# sBoardUS.net
KiCad netlist of a schematic drawn in EAGLE
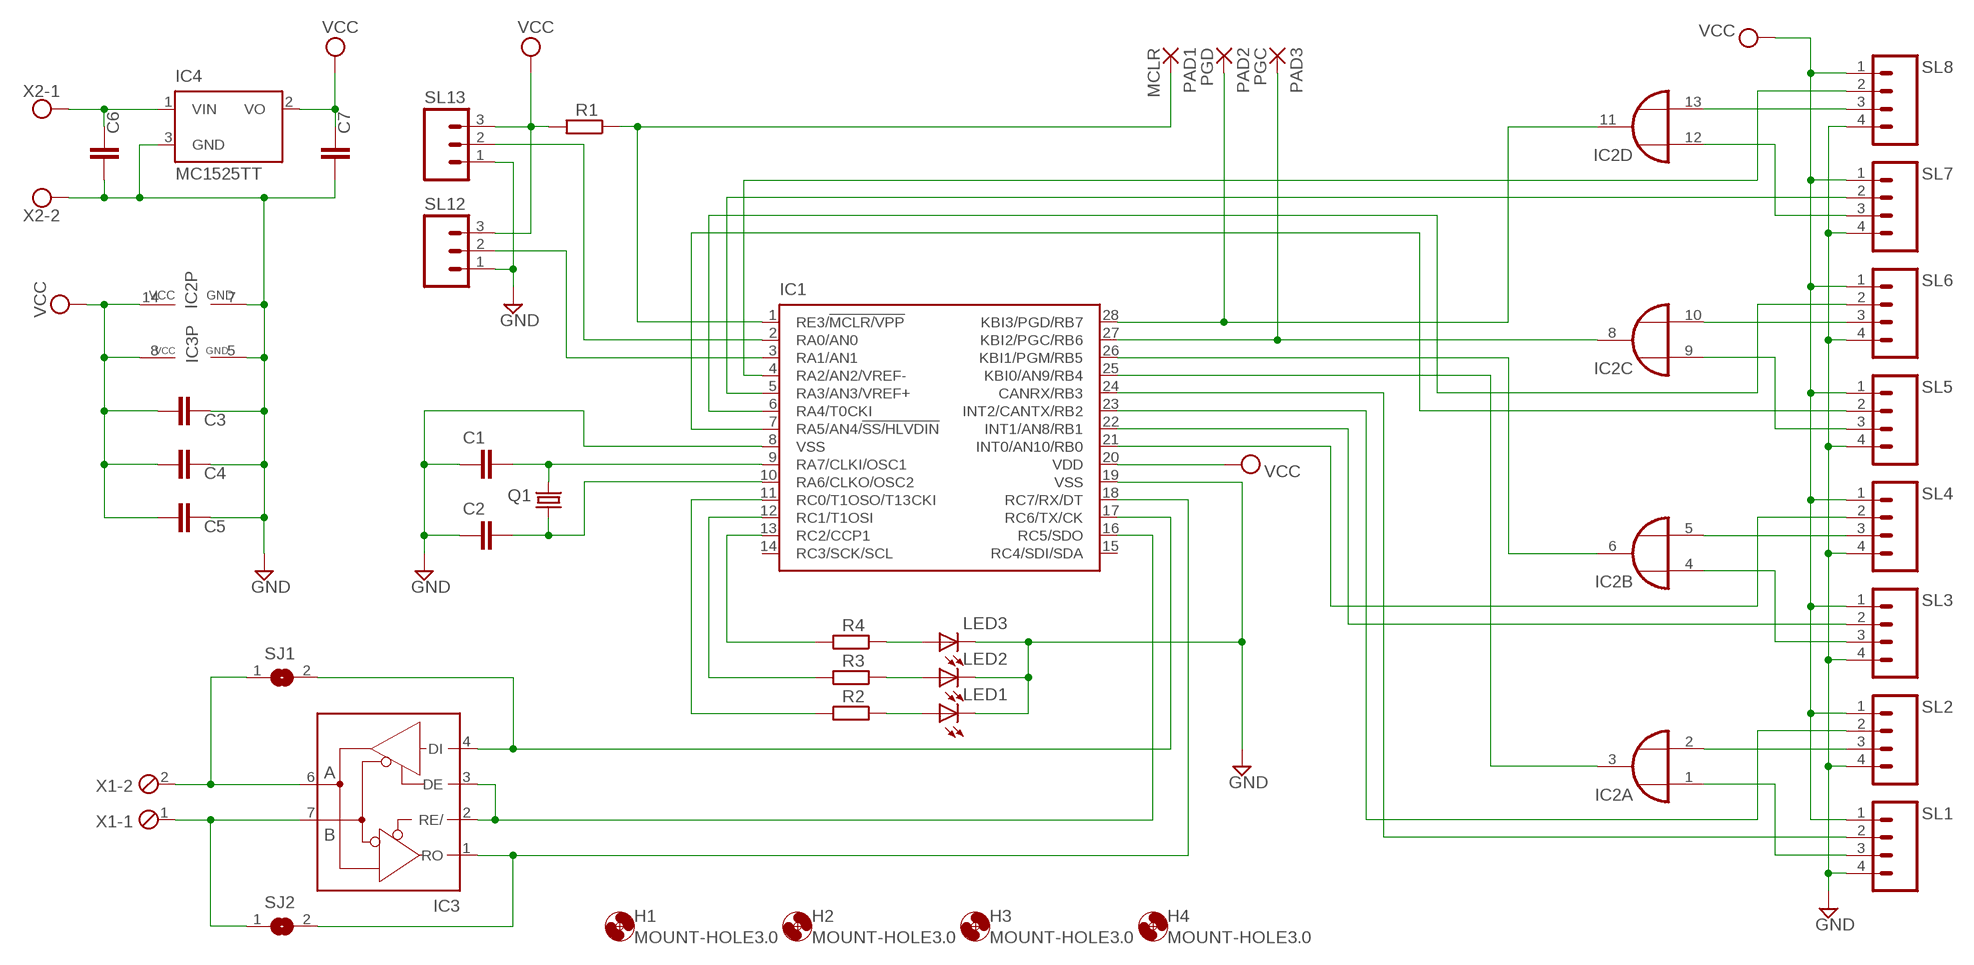
[diagram p0: schematic, sheet 1]

(export (version "E")
  (design (tool "Eeschema 10.0.6"))
  (components
    (comp (ref "C1")
      (value "C-EUC0805")
      (footprint "eagle-import:C0805")
      (libsource (lib "eagle-import") (part "C-EUC0805"))
    )
    (comp (ref "C2")
      (value "C-EUC0805")
      (footprint "eagle-import:C0805")
      (libsource (lib "eagle-import") (part "C-EUC0805"))
    )
    (comp (ref "C3")
      (value "C-EUC0805")
      (footprint "eagle-import:C0805")
      (libsource (lib "eagle-import") (part "C-EUC0805"))
    )
    (comp (ref "C4")
      (value "C-EUC0805")
      (footprint "eagle-import:C0805")
      (libsource (lib "eagle-import") (part "C-EUC0805"))
    )
    (comp (ref "C5")
      (value "C-EUC0805")
      (footprint "eagle-import:C0805")
      (libsource (lib "eagle-import") (part "C-EUC0805"))
    )
    (comp (ref "C6")
      (value "C-EUC0805")
      (footprint "eagle-import:C0805")
      (libsource (lib "eagle-import") (part "C-EUC0805"))
    )
    (comp (ref "C7")
      (value "C-EUC0805")
      (footprint "eagle-import:C0805")
      (libsource (lib "eagle-import") (part "C-EUC0805"))
    )
    (comp (ref "H1")
      (value "MOUNT-HOLE3.0")
      (footprint "eagle-import:3,0")
      (libsource (lib "eagle-import") (part "MOUNT-HOLE3.0"))
    )
    (comp (ref "H2")
      (value "MOUNT-HOLE3.0")
      (footprint "eagle-import:3,0")
      (libsource (lib "eagle-import") (part "MOUNT-HOLE3.0"))
    )
    (comp (ref "H3")
      (value "MOUNT-HOLE3.0")
      (footprint "eagle-import:3,0")
      (libsource (lib "eagle-import") (part "MOUNT-HOLE3.0"))
    )
    (comp (ref "H4")
      (value "MOUNT-HOLE3.0")
      (footprint "eagle-import:3,0")
      (libsource (lib "eagle-import") (part "MOUNT-HOLE3.0"))
    )
    (comp (ref "IC1")
      (value "PIC18F2580-E/SO")
      (footprint "eagle-import:SO28W")
      (fields (field (name "MF") "MICROCHIP") (field (name "MPN") "PIC18F2580-I/SO"))
      (libsource (lib "eagle-import") (part "PIC18F280-E/SO5"))
    )
    (comp (ref "IC2")
      (value "74AC32D")
      (footprint "eagle-import:SO14")
      (libsource (lib "eagle-import") (part "7432DAC"))
    )
    (comp (ref "IC3")
      (value "MAX481CSA")
      (footprint "eagle-import:SO08")
      (fields (field (name "MF") "MAXIM"))
      (libsource (lib "eagle-import") (part "MAX481CSA"))
    )
    (comp (ref "IC4")
      (value "MC1525TT")
      (footprint "eagle-import:SOT23")
      (libsource (lib "eagle-import") (part "MC15TT25"))
    )
    (comp (ref "LED1")
      (value "LED")
      (footprint "eagle-import:SMARTLED-TTW")
      (libsource (lib "eagle-import") (part "LED"))
    )
    (comp (ref "LED2")
      (value "LED")
      (footprint "eagle-import:SMARTLED-TTW")
      (libsource (lib "eagle-import") (part "LED"))
    )
    (comp (ref "LED3")
      (value "LED")
      (footprint "eagle-import:SMARTLED-TTW")
      (libsource (lib "eagle-import") (part "LED"))
    )
    (comp (ref "PAD1")
      (value "MCLR")
      (footprint "eagle-import:SMD1,27-2,54")
      (libsource (lib "eagle-import") (part "SMD2"))
    )
    (comp (ref "PAD2")
      (value "PGD")
      (footprint "eagle-import:SMD1,27-2,54")
      (libsource (lib "eagle-import") (part "SMD2"))
    )
    (comp (ref "PAD3")
      (value "PGC")
      (footprint "eagle-import:SMD1,27-2,54")
      (libsource (lib "eagle-import") (part "SMD2"))
    )
    (comp (ref "Q1")
      (value "CRYSTALHC49UP")
      (footprint "eagle-import:HC49UP")
      (libsource (lib "eagle-import") (part "CRYSTALHC49UP"))
    )
    (comp (ref "R1")
      (value "R-EU_M2012")
      (footprint "eagle-import:M2012")
      (libsource (lib "eagle-import") (part "R-EU_M2012"))
    )
    (comp (ref "R2")
      (value "R-EU_M2012")
      (footprint "eagle-import:M2012")
      (libsource (lib "eagle-import") (part "R-EU_M2012"))
    )
    (comp (ref "R3")
      (value "R-EU_M2012")
      (footprint "eagle-import:M2012")
      (libsource (lib "eagle-import") (part "R-EU_M2012"))
    )
    (comp (ref "R4")
      (value "R-EU_M2012")
      (footprint "eagle-import:M2012")
      (libsource (lib "eagle-import") (part "R-EU_M2012"))
    )
    (comp (ref "SJ1") (value "SJ") (footprint "eagle-import:SJ") (libsource (lib "eagle-import") (part "SJ")))
    (comp (ref "SJ2") (value "SJ") (footprint "eagle-import:SJ") (libsource (lib "eagle-import") (part "SJ")))
    (comp (ref "SL1")
      (value "M04")
      (footprint "eagle-import:04P")
      (libsource (lib "eagle-import") (part "M04"))
    )
    (comp (ref "SL2")
      (value "M04")
      (footprint "eagle-import:04P")
      (libsource (lib "eagle-import") (part "M04"))
    )
    (comp (ref "SL3")
      (value "M04")
      (footprint "eagle-import:04P")
      (libsource (lib "eagle-import") (part "M04"))
    )
    (comp (ref "SL4")
      (value "M04")
      (footprint "eagle-import:04P")
      (libsource (lib "eagle-import") (part "M04"))
    )
    (comp (ref "SL5")
      (value "M04")
      (footprint "eagle-import:04P")
      (libsource (lib "eagle-import") (part "M04"))
    )
    (comp (ref "SL6")
      (value "M04")
      (footprint "eagle-import:04P")
      (libsource (lib "eagle-import") (part "M04"))
    )
    (comp (ref "SL7")
      (value "M04")
      (footprint "eagle-import:04P")
      (libsource (lib "eagle-import") (part "M04"))
    )
    (comp (ref "SL8")
      (value "M04")
      (footprint "eagle-import:04P")
      (libsource (lib "eagle-import") (part "M04"))
    )
    (comp (ref "SL12")
      (value "M03")
      (footprint "eagle-import:03P")
      (libsource (lib "eagle-import") (part "M03"))
    )
    (comp (ref "SL13")
      (value "M03")
      (footprint "eagle-import:03P")
      (libsource (lib "eagle-import") (part "M03"))
    )
    (comp (ref "X1")
      (value "MPT2")
      (footprint "eagle-import:2POL254")
      (libsource (lib "eagle-import") (part "MPT2"))
    )
    (comp (ref "X2")
      (value "AK500/2")
      (footprint "eagle-import:AK500_2")
      (libsource (lib "eagle-import") (part "AK500/2"))
    )
  )
  (nets
    (net (code "1") (name "GND") (class "Default")
      (node (ref "C1") (pin "1") (pinfunction "1_1") (pintype "passive"))
      (node (ref "C2") (pin "1") (pinfunction "1_1") (pintype "passive"))
      (node (ref "C3") (pin "1") (pinfunction "1_1") (pintype "passive"))
      (node (ref "C4") (pin "1") (pinfunction "1_1") (pintype "passive"))
      (node (ref "C5") (pin "1") (pinfunction "1_1") (pintype "passive"))
      (node (ref "C6") (pin "2") (pinfunction "2_2") (pintype "passive"))
      (node (ref "C7") (pin "2") (pinfunction "2_2") (pintype "passive"))
      (node (ref "IC1") (pin "19") (pinfunction "VSS_19") (pintype "power_in"))
      (node (ref "IC1") (pin "8") (pinfunction "VSS_8") (pintype "power_in"))
      (node (ref "IC2") (pin "7") (pinfunction "GND_7") (pintype "power_in"))
      (node (ref "IC3") (pin "5") (pinfunction "GND_5") (pintype "power_in"))
      (node (ref "IC4") (pin "3") (pinfunction "GND_3") (pintype "passive"))
      (node (ref "LED1") (pin "C@1") (pinfunction "C_C@1") (pintype "passive"))
      (node (ref "LED2") (pin "C@1") (pinfunction "C_C@1") (pintype "passive"))
      (node (ref "LED3") (pin "C@1") (pinfunction "C_C@1") (pintype "passive"))
      (node (ref "SL1") (pin "4") (pinfunction "4_4") (pintype "passive"))
      (node (ref "SL12") (pin "1") (pinfunction "1_1") (pintype "passive"))
      (node (ref "SL13") (pin "1") (pinfunction "1_1") (pintype "passive"))
      (node (ref "SL2") (pin "4") (pinfunction "4_4") (pintype "passive"))
      (node (ref "SL3") (pin "4") (pinfunction "4_4") (pintype "passive"))
      (node (ref "SL4") (pin "4") (pinfunction "4_4") (pintype "passive"))
      (node (ref "SL5") (pin "4") (pinfunction "4_4") (pintype "passive"))
      (node (ref "SL6") (pin "4") (pinfunction "4_4") (pintype "passive"))
      (node (ref "SL7") (pin "4") (pinfunction "4_4") (pintype "passive"))
      (node (ref "SL8") (pin "4") (pinfunction "4_4") (pintype "passive"))
      (node (ref "X2") (pin "2") (pinfunction "KL_2") (pintype "passive"))
    )
    (net (code "2") (name "Net-(IC1-CANRX{slash}RB3)") (class "Default")
      (node (ref "IC1") (pin "24") (pinfunction "CANRX/RB3_24") (pintype "bidirectional"))
      (node (ref "SL1") (pin "2") (pinfunction "2_2") (pintype "passive"))
    )
    (net (code "3") (name "Net-(IC1-INT0{slash}AN10{slash}RB0)") (class "Default")
      (node (ref "IC1") (pin "21") (pinfunction "INT0/AN10/RB0_21") (pintype "bidirectional"))
      (node (ref "SL4") (pin "2") (pinfunction "2_2") (pintype "passive"))
    )
    (net (code "4") (name "Net-(IC1-INT1{slash}AN8{slash}RB1)") (class "Default")
      (node (ref "IC1") (pin "22") (pinfunction "INT1/AN8/RB1_22") (pintype "bidirectional"))
      (node (ref "SL3") (pin "2") (pinfunction "2_2") (pintype "passive"))
    )
    (net (code "5") (name "Net-(IC1-INT2{slash}CANTX{slash}RB2)") (class "Default")
      (node (ref "IC1") (pin "23") (pinfunction "INT2/CANTX/RB2_23") (pintype "bidirectional"))
      (node (ref "SL2") (pin "2") (pinfunction "2_2") (pintype "passive"))
    )
    (net (code "6") (name "Net-(IC1-KBI0{slash}AN9{slash}RB4)") (class "Default")
      (node (ref "IC1") (pin "25") (pinfunction "KBI0/AN9/RB4_25") (pintype "bidirectional"))
      (node (ref "IC2") (pin "3") (pinfunction "O_3") (pintype "output"))
    )
    (net (code "7") (name "Net-(IC1-KBI1{slash}PGM{slash}RB5)") (class "Default")
      (node (ref "IC1") (pin "26") (pinfunction "KBI1/PGM/RB5_26") (pintype "bidirectional"))
      (node (ref "IC2") (pin "6") (pinfunction "O_6") (pintype "output"))
    )
    (net (code "8") (name "Net-(IC1-KBI2{slash}PGC{slash}RB6)") (class "Default")
      (node (ref "IC1") (pin "27") (pinfunction "KBI2/PGC/RB6_27") (pintype "bidirectional"))
      (node (ref "IC2") (pin "8") (pinfunction "O_8") (pintype "output"))
      (node (ref "PAD3") (pin "1") (pinfunction "P_1") (pintype "passive"))
    )
    (net (code "9") (name "Net-(IC1-KBI3{slash}PGD{slash}RB7)") (class "Default")
      (node (ref "IC1") (pin "28") (pinfunction "KBI3/PGD/RB7_28") (pintype "bidirectional"))
      (node (ref "IC2") (pin "11") (pinfunction "O_11") (pintype "output"))
      (node (ref "PAD2") (pin "1") (pinfunction "P_1") (pintype "passive"))
    )
    (net (code "10") (name "Net-(IC1-RA0{slash}AN0)") (class "Default")
      (node (ref "IC1") (pin "2") (pinfunction "RA0/AN0_2") (pintype "bidirectional"))
      (node (ref "SL13") (pin "2") (pinfunction "2_2") (pintype "passive"))
    )
    (net (code "11") (name "Net-(IC1-RA1{slash}AN1)") (class "Default")
      (node (ref "IC1") (pin "3") (pinfunction "RA1/AN1_3") (pintype "bidirectional"))
      (node (ref "SL12") (pin "2") (pinfunction "2_2") (pintype "passive"))
    )
    (net (code "12") (name "Net-(IC1-RA2{slash}AN2{slash}VREF-)") (class "Default")
      (node (ref "IC1") (pin "4") (pinfunction "RA2/AN2/VREF-_4") (pintype "bidirectional"))
      (node (ref "SL8") (pin "2") (pinfunction "2_2") (pintype "passive"))
    )
    (net (code "13") (name "Net-(IC1-RA3{slash}AN3{slash}VREF+)") (class "Default")
      (node (ref "IC1") (pin "5") (pinfunction "RA3/AN3/VREF+_5") (pintype "bidirectional"))
      (node (ref "SL7") (pin "2") (pinfunction "2_2") (pintype "passive"))
    )
    (net (code "14") (name "Net-(IC1-RA4{slash}T0CKI)") (class "Default")
      (node (ref "IC1") (pin "6") (pinfunction "RA4/T0CKI_6") (pintype "bidirectional"))
      (node (ref "SL6") (pin "2") (pinfunction "2_2") (pintype "passive"))
    )
    (net (code "15") (name "Net-(IC1-RA5{slash}AN4{slash}~{SS{slash}HLVDIN})") (class "Default")
      (node (ref "IC1") (pin "7") (pinfunction "RA5/AN4/~{SS/HLVDIN}_7") (pintype "bidirectional"))
      (node (ref "SL5") (pin "2") (pinfunction "2_2") (pintype "passive"))
    )
    (net (code "16") (name "Net-(IC1-RA6{slash}CLKO{slash}OSC2)") (class "Default")
      (node (ref "C2") (pin "2") (pinfunction "2_2") (pintype "passive"))
      (node (ref "IC1") (pin "10") (pinfunction "RA6/CLKO/OSC2_10") (pintype "output"))
      (node (ref "Q1") (pin "1") (pinfunction "1_1") (pintype "passive"))
    )
    (net (code "17") (name "Net-(IC1-RA7{slash}CLKI{slash}OSC1)") (class "Default")
      (node (ref "C1") (pin "2") (pinfunction "2_2") (pintype "passive"))
      (node (ref "IC1") (pin "9") (pinfunction "RA7/CLKI/OSC1_9") (pintype "input"))
      (node (ref "Q1") (pin "2") (pinfunction "2_2") (pintype "passive"))
    )
    (net (code "18") (name "Net-(IC1-RC0{slash}T1OSO{slash}T13CKI)") (class "Default")
      (node (ref "IC1") (pin "11") (pinfunction "RC0/T1OSO/T13CKI_11") (pintype "bidirectional"))
      (node (ref "R2") (pin "2") (pinfunction "2_2") (pintype "passive"))
    )
    (net (code "19") (name "Net-(IC1-RC1{slash}T1OSI)") (class "Default")
      (node (ref "IC1") (pin "12") (pinfunction "RC1/T1OSI_12") (pintype "bidirectional"))
      (node (ref "R3") (pin "2") (pinfunction "2_2") (pintype "passive"))
    )
    (net (code "20") (name "Net-(IC1-RC2{slash}CCP1)") (class "Default")
      (node (ref "IC1") (pin "13") (pinfunction "RC2/CCP1_13") (pintype "bidirectional"))
      (node (ref "R4") (pin "2") (pinfunction "2_2") (pintype "passive"))
    )
    (net (code "21") (name "Net-(IC1-RC5{slash}SDO)") (class "Default")
      (node (ref "IC1") (pin "16") (pinfunction "RC5/SDO_16") (pintype "bidirectional"))
      (node (ref "IC3") (pin "2") (pinfunction "RE/_2") (pintype "input"))
      (node (ref "IC3") (pin "3") (pinfunction "DE_3") (pintype "input"))
    )
    (net (code "22") (name "Net-(IC1-RC6{slash}TX{slash}CK)") (class "Default")
      (node (ref "IC1") (pin "17") (pinfunction "RC6/TX/CK_17") (pintype "bidirectional"))
      (node (ref "IC3") (pin "4") (pinfunction "DI_4") (pintype "input"))
      (node (ref "SJ1") (pin "2") (pinfunction "2_2") (pintype "passive"))
    )
    (net (code "23") (name "Net-(IC1-RC7{slash}RX{slash}DT)") (class "Default")
      (node (ref "IC1") (pin "18") (pinfunction "RC7/RX/DT_18") (pintype "bidirectional"))
      (node (ref "IC3") (pin "1") (pinfunction "RO_1") (pintype "output"))
      (node (ref "SJ2") (pin "2") (pinfunction "2_2") (pintype "passive"))
    )
    (net (code "24") (name "Net-(IC1-RE3{slash}~{MCLR{slash}VPP})") (class "Default")
      (node (ref "IC1") (pin "1") (pinfunction "RE3/~{MCLR/VPP}_1") (pintype "input"))
      (node (ref "PAD1") (pin "1") (pinfunction "P_1") (pintype "passive"))
      (node (ref "R1") (pin "1") (pinfunction "1_1") (pintype "passive"))
    )
    (net (code "25") (name "Net-(IC2A-I0)") (class "Default")
      (node (ref "IC2") (pin "1") (pinfunction "I0_1") (pintype "input"))
      (node (ref "SL1") (pin "3") (pinfunction "3_3") (pintype "passive"))
    )
    (net (code "26") (name "Net-(IC2A-I1)") (class "Default")
      (node (ref "IC2") (pin "2") (pinfunction "I1_2") (pintype "input"))
      (node (ref "SL2") (pin "3") (pinfunction "3_3") (pintype "passive"))
    )
    (net (code "27") (name "Net-(IC2B-I0)") (class "Default")
      (node (ref "IC2") (pin "4") (pinfunction "I0_4") (pintype "input"))
      (node (ref "SL3") (pin "3") (pinfunction "3_3") (pintype "passive"))
    )
    (net (code "28") (name "Net-(IC2B-I1)") (class "Default")
      (node (ref "IC2") (pin "5") (pinfunction "I1_5") (pintype "input"))
      (node (ref "SL4") (pin "3") (pinfunction "3_3") (pintype "passive"))
    )
    (net (code "29") (name "Net-(IC2C-I0)") (class "Default")
      (node (ref "IC2") (pin "9") (pinfunction "I0_9") (pintype "input"))
      (node (ref "SL5") (pin "3") (pinfunction "3_3") (pintype "passive"))
    )
    (net (code "30") (name "Net-(IC2C-I1)") (class "Default")
      (node (ref "IC2") (pin "10") (pinfunction "I1_10") (pintype "input"))
      (node (ref "SL6") (pin "3") (pinfunction "3_3") (pintype "passive"))
    )
    (net (code "31") (name "Net-(IC2D-I0)") (class "Default")
      (node (ref "IC2") (pin "12") (pinfunction "I0_12") (pintype "input"))
      (node (ref "SL7") (pin "3") (pinfunction "3_3") (pintype "passive"))
    )
    (net (code "32") (name "Net-(IC2D-I1)") (class "Default")
      (node (ref "IC2") (pin "13") (pinfunction "I1_13") (pintype "input"))
      (node (ref "SL8") (pin "3") (pinfunction "3_3") (pintype "passive"))
    )
    (net (code "33") (name "Net-(IC3A-A)") (class "Default")
      (node (ref "IC3") (pin "6") (pinfunction "A_6") (pintype "passive"))
      (node (ref "SJ1") (pin "1") (pinfunction "1_1") (pintype "passive"))
      (node (ref "X1") (pin "2") (pinfunction "1_2") (pintype "passive"))
    )
    (net (code "34") (name "Net-(IC3A-B)") (class "Default")
      (node (ref "IC3") (pin "7") (pinfunction "B_7") (pintype "passive"))
      (node (ref "SJ2") (pin "1") (pinfunction "1_1") (pintype "passive"))
      (node (ref "X1") (pin "1") (pinfunction "1_1") (pintype "passive"))
    )
    (net (code "35") (name "Net-(IC4-VIN)") (class "Default")
      (node (ref "C6") (pin "1") (pinfunction "1_1") (pintype "passive"))
      (node (ref "IC4") (pin "1") (pinfunction "VIN_1") (pintype "input"))
      (node (ref "X2") (pin "1") (pinfunction "KL_1") (pintype "passive"))
    )
    (net (code "36") (name "Net-(LED1-A)") (class "Default")
      (node (ref "LED1") (pin "A@1") (pinfunction "A_A@1") (pintype "passive"))
      (node (ref "R2") (pin "1") (pinfunction "1_1") (pintype "passive"))
    )
    (net (code "37") (name "Net-(LED2-A)") (class "Default")
      (node (ref "LED2") (pin "A@1") (pinfunction "A_A@1") (pintype "passive"))
      (node (ref "R3") (pin "1") (pinfunction "1_1") (pintype "passive"))
    )
    (net (code "38") (name "Net-(LED3-A)") (class "Default")
      (node (ref "LED3") (pin "A@1") (pinfunction "A_A@1") (pintype "passive"))
      (node (ref "R4") (pin "1") (pinfunction "1_1") (pintype "passive"))
    )
    (net (code "39") (name "VCC") (class "Default")
      (node (ref "C3") (pin "2") (pinfunction "2_2") (pintype "passive"))
      (node (ref "C4") (pin "2") (pinfunction "2_2") (pintype "passive"))
      (node (ref "C5") (pin "2") (pinfunction "2_2") (pintype "passive"))
      (node (ref "C7") (pin "1") (pinfunction "1_1") (pintype "passive"))
      (node (ref "IC1") (pin "20") (pinfunction "VDD_20") (pintype "power_in"))
      (node (ref "IC2") (pin "14") (pinfunction "VCC_14") (pintype "power_in"))
      (node (ref "IC3") (pin "8") (pinfunction "VCC_8") (pintype "power_in"))
      (node (ref "IC4") (pin "2") (pinfunction "VO_2") (pintype "output"))
      (node (ref "R1") (pin "2") (pinfunction "2_2") (pintype "passive"))
      (node (ref "SL1") (pin "1") (pinfunction "1_1") (pintype "passive"))
      (node (ref "SL12") (pin "3") (pinfunction "3_3") (pintype "passive"))
      (node (ref "SL13") (pin "3") (pinfunction "3_3") (pintype "passive"))
      (node (ref "SL2") (pin "1") (pinfunction "1_1") (pintype "passive"))
      (node (ref "SL3") (pin "1") (pinfunction "1_1") (pintype "passive"))
      (node (ref "SL4") (pin "1") (pinfunction "1_1") (pintype "passive"))
      (node (ref "SL5") (pin "1") (pinfunction "1_1") (pintype "passive"))
      (node (ref "SL6") (pin "1") (pinfunction "1_1") (pintype "passive"))
      (node (ref "SL7") (pin "1") (pinfunction "1_1") (pintype "passive"))
      (node (ref "SL8") (pin "1") (pinfunction "1_1") (pintype "passive"))
    )
    (net (code "40") (name "unconnected-(IC1-RC3{slash}SCK{slash}SCL-Pad14)") (class "Default")
      (node (ref "IC1") (pin "14") (pinfunction "RC3/SCK/SCL_14") (pintype "bidirectional"))
    )
    (net (code "41") (name "unconnected-(IC1-RC4{slash}SDI{slash}SDA-Pad15)") (class "Default")
      (node (ref "IC1") (pin "15") (pinfunction "RC4/SDI/SDA_15") (pintype "bidirectional"))
    )
  )
)
